# Motor_Control_PCB_Schematic.net
KiCad netlist of a schematic drawn in Altium Designer
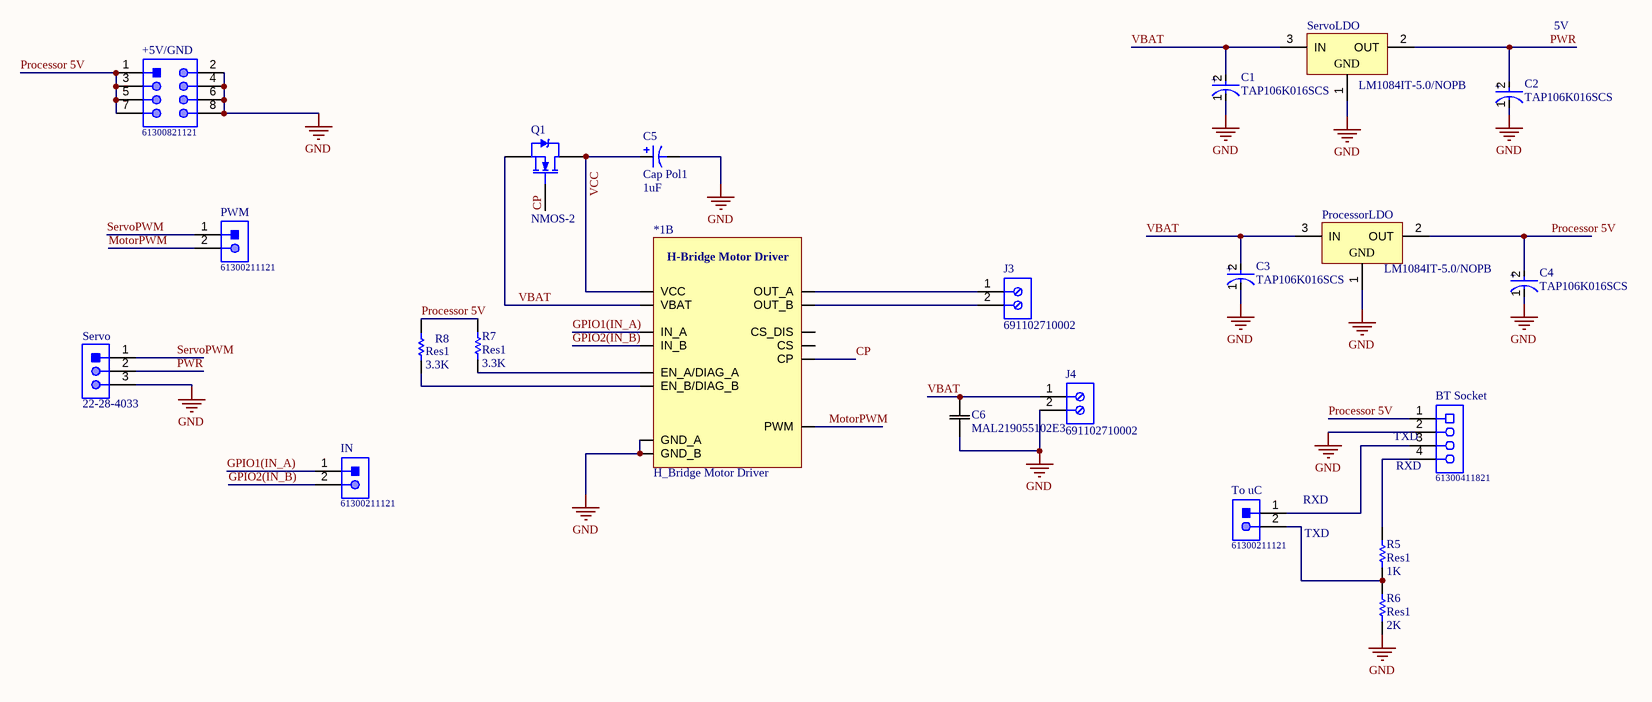
[diagram p0: Motor_Control_PCB_Schematic.SchDoc]

(export (version "E")
  (design (tool "Eeschema 10.0.6"))
  (components
    (comp (ref "*1")
      (value "H_Bridge Motor Driver")
      (footprint "H-bridge Motor Driver (Lab1)")
      (libsource (lib "SeniorDesign") (part "H_Bridge Motor Driver"))
    )
    (comp (ref "+5V/GND")
      (value "61300821121")
      (footprint "61300821121")
      (description "THT Vertical Pin Header WR-PHD, Pitch 2.54 mm, Dual Row, 8 pins")
      (fields (field (name "MANUFACTURER") "Wurth Elektronik") (field (name "PUBLISHER") "WurthElektronik"))
      (libsource (lib "Altium Content Vault") (part "WE-CN-2P-M-R8"))
    )
    (comp (ref "BT Socket")
      (value "61300411821")
      (footprint "61300411821")
      (description "THT Vertical Socket Header WR-PHD, Pitch 2.54 mm, Single Row, 4 pins")
      (fields (field (name "MANUFACTURER") "Wurth Elektronik") (field (name "PUBLISHER") "WurthElektronik"))
      (libsource (lib "Altium Content Vault") (part "WE-CN-1P-F-R4"))
    )
    (comp (ref "C1")
      (value "TAP106K016SCS")
      (footprint "FP-TAP106K016SCS-MFG")
      (description "CAP TANT 10UF 10% 16V RADIAL")
      (fields (field (name "TOLERANCE") "10%") (field (name "VOLTAGE") "16V"))
      (libsource (lib "Altium Content Vault") (part "cf48714ba7e38822c1575c7ec0b6d1f"))
    )
    (comp (ref "C2")
      (value "TAP106K016SCS")
      (footprint "FP-TAP106K016SCS-MFG")
      (description "CAP TANT 10UF 10% 16V RADIAL")
      (fields (field (name "TOLERANCE") "10%") (field (name "VOLTAGE") "16V"))
      (libsource (lib "Altium Content Vault") (part "cf48714ba7e38822c1575c7ec0b6d1f"))
    )
    (comp (ref "C3")
      (value "TAP106K016SCS")
      (footprint "FP-TAP106K016SCS-MFG")
      (description "CAP TANT 10UF 10% 16V RADIAL")
      (fields (field (name "TOLERANCE") "10%") (field (name "VOLTAGE") "16V"))
      (libsource (lib "Altium Content Vault") (part "cf48714ba7e38822c1575c7ec0b6d1f"))
    )
    (comp (ref "C4")
      (value "TAP106K016SCS")
      (footprint "FP-TAP106K016SCS-MFG")
      (description "CAP TANT 10UF 10% 16V RADIAL")
      (fields (field (name "TOLERANCE") "10%") (field (name "VOLTAGE") "16V"))
      (libsource (lib "Altium Content Vault") (part "cf48714ba7e38822c1575c7ec0b6d1f"))
    )
    (comp (ref "C5")
      (value "Cap Pol1")
      (footprint "RB7.6-15")
      (description "Polarized Capacitor (Radial)")
      (fields (field (name "ALTIUM_VALUE") "1uF") (field (name "PUBLISHER") "Altium Limited"))
      (libsource (lib "Miscellaneous Devices") (part "Cap Pol1"))
    )
    (comp (ref "C6")
      (value "MAL219055102E3")
      (footprint "CAP_5102E3_VIS")
      (description "No Description Available")
      (fields (field (name "COPYRIGHT") "Copyright (C) 2023 Ultra Librarian. All rights reserved."))
      (libsource (lib "MAL219055102E3") (part "MAL219055102E3"))
    )
    (comp (ref "IN")
      (value "61300211121")
      (footprint "61300211121")
      (description "THT Vertical Pin Header WR-PHD, Pitch 2.54 mm, Single Row, 2 pins")
      (fields (field (name "MANUFACTURER") "Wurth Elektronik") (field (name "PUBLISHER") "WurthElektronik"))
      (libsource (lib "") (part "WE-CN-1P-M-R2_1"))
    )
    (comp (ref "J3")
      (value "691102710002")
      (footprint "691102710002")
      (description "Series 102 - 5.00 mm Horizontal Entry Modular with Pressure Clamp WR-TBL, 2 pin")
      (fields (field (name "MANUFACTURER") "Wurth Elektronik") (field (name "PUBLISHER") "WurthElektronik"))
      (libsource (lib "Altium Content Vault") (part "WE-CN-1P-F-TB2"))
    )
    (comp (ref "J4")
      (value "691102710002")
      (footprint "691102710002")
      (description "Series 102 - 5.00 mm Horizontal Entry Modular with Pressure Clamp WR-TBL, 2 pin")
      (fields (field (name "MANUFACTURER") "Wurth Elektronik") (field (name "PUBLISHER") "WurthElektronik"))
      (libsource (lib "Altium Content Vault") (part "WE-CN-1P-F-TB2"))
    )
    (comp (ref "ProcessorLDO")
      (value "LM1084IT-5.0/NOPB")
      (footprint "NDE0003A")
      (description "5A Low Dropout Positive Regulators, 3-pin TO-220, Pb-Free")
      (fields (field (name "MANUFACTURER") "Texas Instruments"))
      (libsource (lib "Altium Content Vault") (part "PM-REG-LM1086-SIL3"))
    )
    (comp (ref "PWM")
      (value "61300211121")
      (footprint "61300211121")
      (description "THT Vertical Pin Header WR-PHD, Pitch 2.54 mm, Single Row, 2 pins")
      (fields (field (name "MANUFACTURER") "Wurth Elektronik") (field (name "PUBLISHER") "WurthElektronik"))
      (libsource (lib "") (part "WE-CN-1P-M-R2_1"))
    )
    (comp (ref "Q1")
      (value "NMOS-2")
      (footprint "TO-220AB")
      (description "N-Channel Power MOSFET")
      (fields (field (name "PUBLISHER") "Altium Limited"))
      (libsource (lib "Miscellaneous Devices") (part "NMOS-2"))
    )
    (comp (ref "R5")
      (value "Res1")
      (footprint "AXIAL-0.3")
      (description "Resistor")
      (fields (field (name "ALTIUM_VALUE") "1K") (field (name "PUBLISHER") "Altium Limited"))
      (libsource (lib "Miscellaneous Devices") (part "Res1"))
    )
    (comp (ref "R6")
      (value "Res1")
      (footprint "AXIAL-0.3")
      (description "Resistor")
      (fields (field (name "ALTIUM_VALUE") "2K") (field (name "PUBLISHER") "Altium Limited"))
      (libsource (lib "Miscellaneous Devices") (part "Res1"))
    )
    (comp (ref "R7")
      (value "Res1")
      (footprint "AXIAL-0.3")
      (description "Resistor")
      (fields (field (name "ALTIUM_VALUE") "3.3K") (field (name "PUBLISHER") "Altium Limited"))
      (libsource (lib "Miscellaneous Devices") (part "Res1"))
    )
    (comp (ref "R8")
      (value "Res1")
      (footprint "AXIAL-0.3")
      (description "Resistor")
      (fields (field (name "ALTIUM_VALUE") "3.3K") (field (name "PUBLISHER") "Altium Limited"))
      (libsource (lib "Miscellaneous Devices") (part "Res1"))
    )
    (comp (ref "Servo")
      (value "22-28-4033")
      (footprint "MOLX-22-28-4033_V")
      (description "Male Header, Pitch 2.54 mm, 1 x 3 Position, Height 8.38 mm, Tail Length 3.18 mm, RoHS, Bulk")
      (fields (field (name "MANUFACTURER") "Molex"))
      (libsource (lib "Altium Content Vault") (part "CN-1P-M-R3"))
    )
    (comp (ref "ServoLDO")
      (value "LM1084IT-5.0/NOPB")
      (footprint "NDE0003A")
      (description "5A Low Dropout Positive Regulators, 3-pin TO-220, Pb-Free")
      (fields (field (name "MANUFACTURER") "Texas Instruments"))
      (libsource (lib "Altium Content Vault") (part "PM-REG-LM1086-SIL3"))
    )
    (comp (ref "To uC")
      (value "61300211121")
      (footprint "61300211121")
      (description "THT Vertical Pin Header WR-PHD, Pitch 2.54 mm, Single Row, 2 pins")
      (fields (field (name "MANUFACTURER") "Wurth Elektronik") (field (name "PUBLISHER") "WurthElektronik"))
      (libsource (lib "Altium Content Vault") (part "WE-CN-1P-M-R2"))
    )
  )
  (nets
    (net (code "1") (name "/CP") (class "Default")
      (node (ref "*1") (pin "CP") (pinfunction "CP_CP") (pintype "passive"))
      (node (ref "Q1") (pin "1") (pinfunction "G_1") (pintype "passive"))
    )
    (net (code "2") (name "/GPIO1(IN_A)") (class "Default")
      (node (ref "*1") (pin "IN_A") (pinfunction "IN_A_IN_A") (pintype "passive"))
      (node (ref "IN") (pin "1") (pinfunction "1_1") (pintype "passive"))
    )
    (net (code "3") (name "/GPIO2(IN_B)") (class "Default")
      (node (ref "*1") (pin "IN_B") (pinfunction "IN_B_IN_B") (pintype "passive"))
      (node (ref "IN") (pin "2") (pinfunction "2_2") (pintype "passive"))
    )
    (net (code "4") (name "/MotorPWM") (class "Default")
      (node (ref "*1") (pin "PWM") (pinfunction "PWM_PWM") (pintype "passive"))
      (node (ref "PWM") (pin "2") (pinfunction "2_2") (pintype "passive"))
    )
    (net (code "5") (name "/PWR") (class "Default")
      (node (ref "C2") (pin "2") (pinfunction "A_2") (pintype "passive"))
      (node (ref "Servo") (pin "2") (pinfunction "2_2") (pintype "passive"))
      (node (ref "ServoLDO") (pin "2") (pinfunction "OUT_2") (pintype "power_in"))
    )
    (net (code "6") (name "/Processor 5V") (class "Default")
      (node (ref "+5V/GND") (pin "1") (pinfunction "1_1") (pintype "passive"))
      (node (ref "+5V/GND") (pin "3") (pinfunction "3_3") (pintype "passive"))
      (node (ref "+5V/GND") (pin "5") (pinfunction "5_5") (pintype "passive"))
      (node (ref "+5V/GND") (pin "7") (pinfunction "7_7") (pintype "passive"))
      (node (ref "BT Socket") (pin "1") (pinfunction "1_1") (pintype "passive"))
      (node (ref "C4") (pin "2") (pinfunction "A_2") (pintype "passive"))
      (node (ref "ProcessorLDO") (pin "2") (pinfunction "OUT_2") (pintype "power_in"))
      (node (ref "R7") (pin "2") (pinfunction "2_2") (pintype "passive"))
      (node (ref "R8") (pin "2") (pinfunction "2_2") (pintype "passive"))
    )
    (net (code "7") (name "/ServoPWM") (class "Default")
      (node (ref "PWM") (pin "1") (pinfunction "1_1") (pintype "passive"))
      (node (ref "Servo") (pin "1") (pinfunction "1_1") (pintype "passive"))
    )
    (net (code "8") (name "/VBAT") (class "Default")
      (node (ref "*1") (pin "VBAT") (pinfunction "VBAT_VBAT") (pintype "passive"))
      (node (ref "C1") (pin "2") (pinfunction "A_2") (pintype "passive"))
      (node (ref "C3") (pin "2") (pinfunction "A_2") (pintype "passive"))
      (node (ref "C6") (pin "2") (pinfunction "2_2") (pintype "passive"))
      (node (ref "J4") (pin "1") (pinfunction "1_1") (pintype "passive"))
      (node (ref "ProcessorLDO") (pin "3") (pinfunction "IN_3") (pintype "power_in"))
      (node (ref "Q1") (pin "3") (pinfunction "S_3") (pintype "passive"))
      (node (ref "ServoLDO") (pin "3") (pinfunction "IN_3") (pintype "power_in"))
    )
    (net (code "9") (name "/VCC") (class "Default")
      (node (ref "*1") (pin "VCC") (pinfunction "VCC_VCC") (pintype "passive"))
      (node (ref "C5") (pin "1") (pinfunction "1_1") (pintype "passive"))
      (node (ref "Q1") (pin "2") (pinfunction "D_2") (pintype "passive"))
    )
    (net (code "10") (name "GND") (class "Default")
      (node (ref "*1") (pin "GND_A") (pinfunction "GND_A_GND_A") (pintype "passive"))
      (node (ref "*1") (pin "GND_B") (pinfunction "GND_B_GND_B") (pintype "passive"))
      (node (ref "+5V/GND") (pin "2") (pinfunction "2_2") (pintype "passive"))
      (node (ref "+5V/GND") (pin "4") (pinfunction "4_4") (pintype "passive"))
      (node (ref "+5V/GND") (pin "6") (pinfunction "6_6") (pintype "passive"))
      (node (ref "+5V/GND") (pin "8") (pinfunction "8_8") (pintype "passive"))
      (node (ref "BT Socket") (pin "2") (pinfunction "2_2") (pintype "passive"))
      (node (ref "C1") (pin "1") (pinfunction "C_1") (pintype "passive"))
      (node (ref "C2") (pin "1") (pinfunction "C_1") (pintype "passive"))
      (node (ref "C3") (pin "1") (pinfunction "C_1") (pintype "passive"))
      (node (ref "C4") (pin "1") (pinfunction "C_1") (pintype "passive"))
      (node (ref "C5") (pin "2") (pinfunction "2_2") (pintype "passive"))
      (node (ref "C6") (pin "1") (pinfunction "1_1") (pintype "passive"))
      (node (ref "J4") (pin "2") (pinfunction "2_2") (pintype "passive"))
      (node (ref "ProcessorLDO") (pin "1") (pinfunction "GND_1") (pintype "power_in"))
      (node (ref "R6") (pin "1") (pinfunction "1_1") (pintype "passive"))
      (node (ref "Servo") (pin "3") (pinfunction "3_3") (pintype "passive"))
      (node (ref "ServoLDO") (pin "1") (pinfunction "GND_1") (pintype "power_in"))
    )
    (net (code "11") (name "Net-(*1-PadEN_A{slash}DIAG_A)") (class "Default")
      (node (ref "*1") (pin "EN_A/DIAG_A") (pinfunction "EN_A/DIAG_A_EN_A/DIAG_A") (pintype "passive"))
      (node (ref "R7") (pin "1") (pinfunction "1_1") (pintype "passive"))
    )
    (net (code "12") (name "Net-(*1-PadEN_B{slash}DIAG_B)") (class "Default")
      (node (ref "*1") (pin "EN_B/DIAG_B") (pinfunction "EN_B/DIAG_B_EN_B/DIAG_B") (pintype "passive"))
      (node (ref "R8") (pin "1") (pinfunction "1_1") (pintype "passive"))
    )
    (net (code "13") (name "Net-(*1-PadOUT_A)") (class "Default")
      (node (ref "*1") (pin "OUT_A") (pinfunction "OUT_A_OUT_A") (pintype "passive"))
      (node (ref "J3") (pin "1") (pinfunction "1_1") (pintype "passive"))
    )
    (net (code "14") (name "Net-(*1-PadOUT_B)") (class "Default")
      (node (ref "*1") (pin "OUT_B") (pinfunction "OUT_B_OUT_B") (pintype "passive"))
      (node (ref "J3") (pin "2") (pinfunction "2_2") (pintype "passive"))
    )
    (net (code "15") (name "Net-(BT Socket-Pad3)") (class "Default")
      (node (ref "BT Socket") (pin "3") (pinfunction "3_3") (pintype "passive"))
      (node (ref "To uC") (pin "1") (pinfunction "1_1") (pintype "passive"))
    )
    (net (code "16") (name "Net-(BT Socket-Pad4)") (class "Default")
      (node (ref "BT Socket") (pin "4") (pinfunction "4_4") (pintype "passive"))
      (node (ref "R5") (pin "2") (pinfunction "2_2") (pintype "passive"))
    )
    (net (code "17") (name "Net-(R5-Pad1)") (class "Default")
      (node (ref "R5") (pin "1") (pinfunction "1_1") (pintype "passive"))
      (node (ref "R6") (pin "2") (pinfunction "2_2") (pintype "passive"))
      (node (ref "To uC") (pin "2") (pinfunction "2_2") (pintype "passive"))
    )
    (net (code "18") (name "unconnected-(*1-PadCS)") (class "Default")
      (node (ref "*1") (pin "CS") (pinfunction "CS_CS") (pintype "passive"))
    )
    (net (code "19") (name "unconnected-(*1-PadCS_DIS)") (class "Default")
      (node (ref "*1") (pin "CS_DIS") (pinfunction "CS_DIS_CS_DIS") (pintype "passive"))
    )
  )
)
